# sharpboard.net
KiCad netlist of a schematic drawn in EAGLE
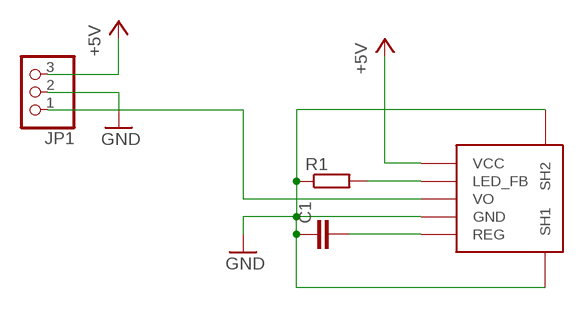
[diagram p0: schematic, sheet 1]

(export (version "E")
  (design (tool "Eeschema 10.0.6"))
  (components
    (comp (ref "C1")
      (value "C-EUC0805")
      (footprint "eagle-import:C0805")
      (libsource (lib "eagle-import") (part "C-EUC0805"))
    )
    (comp (ref "JP1")
      (value "PINHD-1X3")
      (footprint "eagle-import:1X03")
      (libsource (lib "eagle-import") (part "PINHD-1X3"))
    )
    (comp (ref "R1")
      (value "R-EU_R0805")
      (footprint "eagle-import:R0805")
      (libsource (lib "eagle-import") (part "R-EU_R0805"))
    )
    (comp (ref "U$2")
      (value "GP2Y0D340K0F")
      (footprint "eagle-import:GP2Y0D340K0F")
      (libsource (lib "eagle-import") (part "GP2Y0D340K0F"))
    )
  )
  (nets
    (net (code "1") (name "+5V") (class "Default")
      (node (ref "JP1") (pin "3") (pinfunction "3_3") (pintype "passive"))
      (node (ref "U$2") (pin "P$1") (pinfunction "VCC_P$1") (pintype "bidirectional"))
    )
    (net (code "2") (name "GND") (class "Default")
      (node (ref "C1") (pin "1") (pinfunction "1_1") (pintype "passive"))
      (node (ref "JP1") (pin "2") (pinfunction "2_2") (pintype "passive"))
      (node (ref "R1") (pin "1") (pinfunction "1_1") (pintype "passive"))
      (node (ref "U$2") (pin "P$4") (pinfunction "GND_P$4") (pintype "bidirectional"))
      (node (ref "U$2") (pin "P$6") (pinfunction "SH1_P$6") (pintype "bidirectional"))
      (node (ref "U$2") (pin "P$7") (pinfunction "SH2_P$7") (pintype "bidirectional"))
    )
    (net (code "3") (name "Net-(U$2-LED_FB)") (class "Default")
      (node (ref "R1") (pin "2") (pinfunction "2_2") (pintype "passive"))
      (node (ref "U$2") (pin "P$2") (pinfunction "LED_FB_P$2") (pintype "bidirectional"))
    )
    (net (code "4") (name "Net-(U$2-REG)") (class "Default")
      (node (ref "C1") (pin "2") (pinfunction "2_2") (pintype "passive"))
      (node (ref "U$2") (pin "P$5") (pinfunction "REG_P$5") (pintype "bidirectional"))
    )
    (net (code "5") (name "Net-(U$2-VO)") (class "Default")
      (node (ref "JP1") (pin "1") (pinfunction "1_1") (pintype "passive"))
      (node (ref "U$2") (pin "P$3") (pinfunction "VO_P$3") (pintype "bidirectional"))
    )
  )
)
